# ProPrj_mousring_2025-06-12.net
KiCad netlist of a schematic drawn in EasyEDA Pro
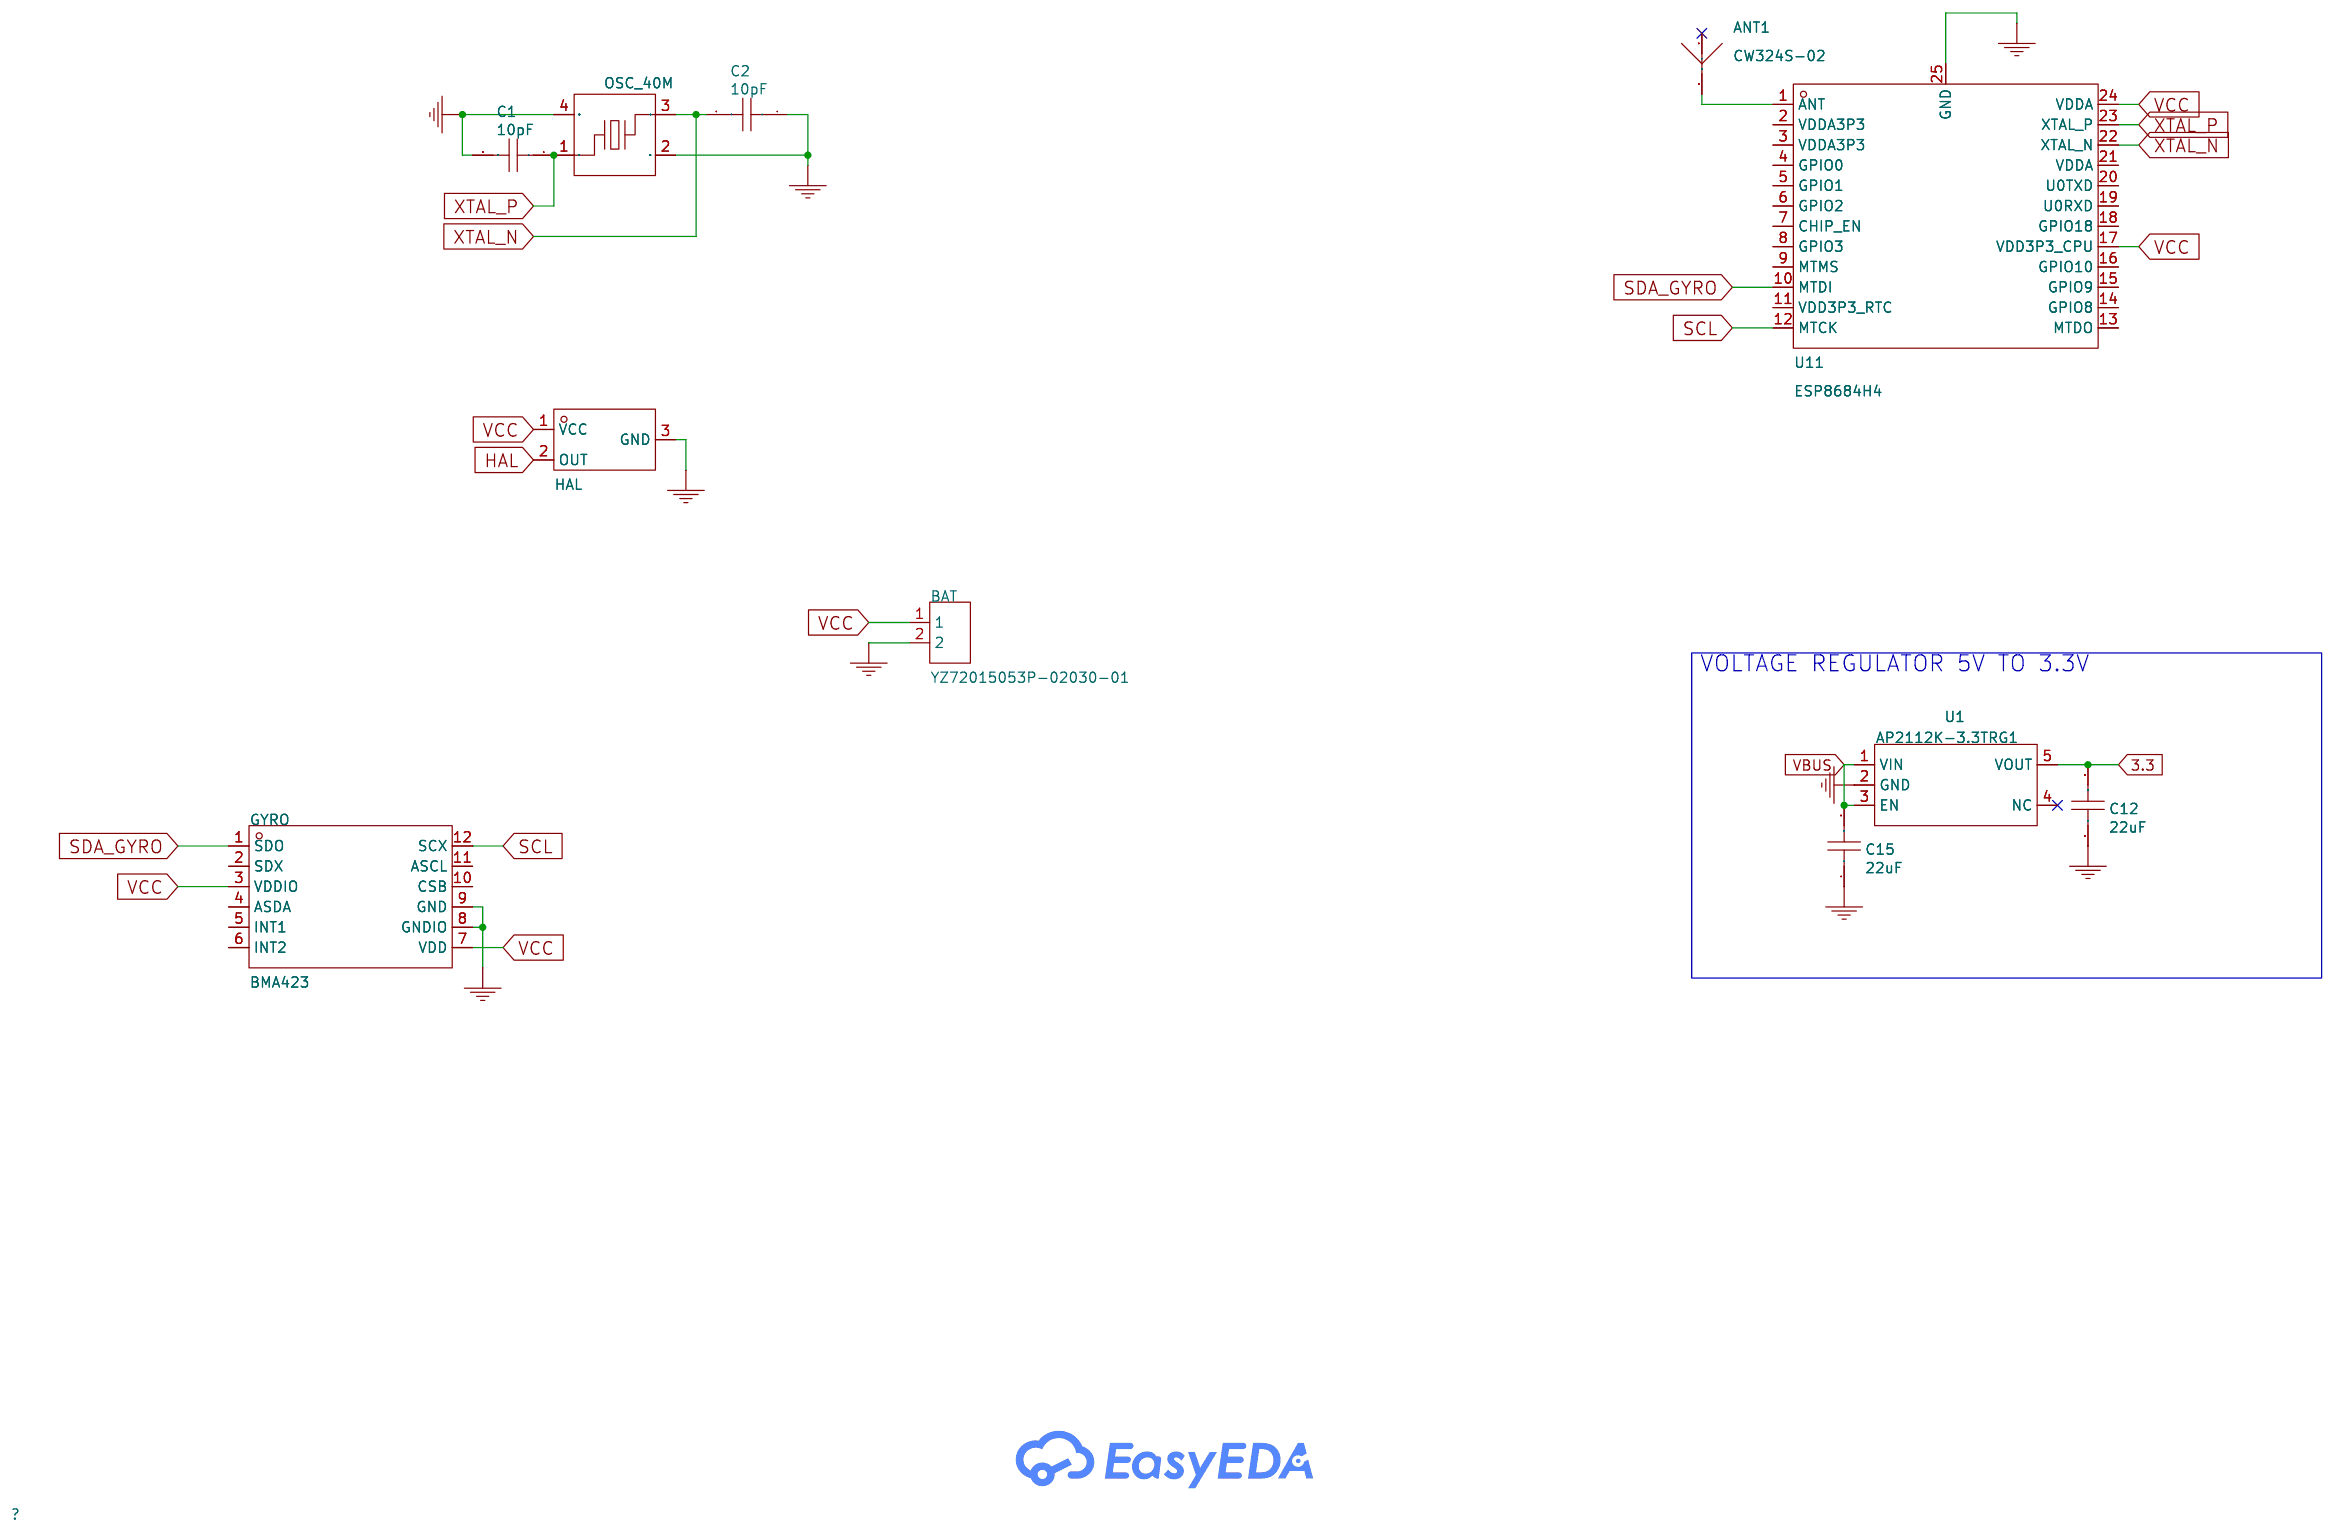
[diagram p0: schematic sheet]

(export (version "E")
  (design (tool "Eeschema 10.0.6"))
  (components
    (comp (ref "ANT1")
      (value "CW324S-02")
      (footprint "easyedapro:ANT-SMD_L3.2-W1.6_CW324S-01")
      (fields (field (name "Manufacturer") "LXC(连兴创)"))
      (libsource (lib "easyedapro") (part "CW324S-02"))
    )
    (comp (ref "BAT")
      (value "YZ72015053P-02030-01")
      (footprint "easyedapro:POGO-SMD_2P-P3.00_YZ72015053P-02030-01")
      (fields (field (name "Manufacturer") "Xinyangze(鑫扬泽)"))
      (libsource (lib "easyedapro") (part "YZ72015053P-02030-01"))
    )
    (comp (ref "C1")
      (value "10pF")
      (footprint "easyedapro:C0402")
      (fields
        (field (name "Manufacturer Part") "CL05C100JB5NNNC")
        (field (name "Manufacturer") "SAMSUNG(三星)")
      )
      (libsource (lib "easyedapro") (part "10pF"))
    )
    (comp (ref "C2")
      (value "10pF")
      (footprint "easyedapro:C0402")
      (fields
        (field (name "Manufacturer Part") "CL05C100JB5NNNC")
        (field (name "Manufacturer") "SAMSUNG(三星)")
      )
      (libsource (lib "easyedapro") (part "10pF"))
    )
    (comp (ref "C12")
      (value "22uF")
      (footprint "easyedapro:C0603")
      (fields
        (field (name "Manufacturer Part") "CL10A226MQ8NRNC")
        (field (name "Manufacturer") "SAMSUNG(三星)")
      )
      (libsource (lib "easyedapro") (part "22uF"))
    )
    (comp (ref "C15")
      (value "22uF")
      (footprint "easyedapro:C0603")
      (fields
        (field (name "Manufacturer Part") "CL10A226MQ8NRNC")
        (field (name "Manufacturer") "SAMSUNG(三星)")
      )
      (libsource (lib "easyedapro") (part "22uF"))
    )
    (comp (ref "GYRO")
      (value "BMA423")
      (footprint "easyedapro:LGA-12_L2.0-W2.0-P0.50-BL")
      (fields (field (name "Manufacturer") "Bosch(博世)"))
      (libsource (lib "easyedapro") (part "BMA423"))
    )
    (comp (ref "U1")
      (value "AP2112K-3.3TRG1")
      (footprint "easyedapro:SOT-25-5_L2.9-W1.6-P0.95-LS2.8-BL")
      (fields (field (name "Manufacturer") "DIODES(美台)") (field (name "Contributor") "LCSC"))
      (libsource (lib "easyedapro") (part "AP2112K-3.3TRG1"))
    )
    (comp (ref "U9")
      (value "HAL")
      (footprint "easyedapro:SOT-23-3_L2.9-W1.6-P1.90-LS2.9-BL")
      (fields (field (name "Manufacturer Part") "HAL3144E") (field (name "Manufacturer") "Hallwee(霍尔微电子)"))
      (libsource (lib "easyedapro") (part "HAL3144E"))
    )
    (comp (ref "U11")
      (value "ESP8684H4")
      (footprint "easyedapro:QFN-24_L4.0-W4.0-P0.50-TL-EP2.8")
      (fields (field (name "Manufacturer") "ESPRESSIF(乐鑫)"))
      (libsource (lib "easyedapro") (part "ESP8684H4"))
    )
    (comp (ref "X1")
      (value "OSC_40M")
      (footprint "easyedapro:CRYSTAL-SMD_4P-L1.6-W1.2-BL")
      (fields
        (field (name "Manufacturer Part") "SX0B40.000F1010F30")
        (field (name "Manufacturer") "SCTF(星通时频)")
        (field (name "Contributor") "lcsc")
      )
      (libsource (lib "easyedapro") (part "40MHz"))
    )
  )
  (nets
    (net (code "1") (name "3.3") (class "Default")
      (node (ref "C12") (pin "2") (pinfunction "2_2") (pintype "unspecified"))
      (node (ref "U1") (pin "5") (pinfunction "VOUT_5") (pintype "unspecified"))
    )
    (net (code "2") (name "GND") (class "Default")
      (node (ref "BAT") (pin "2") (pinfunction "2_2") (pintype "unspecified"))
      (node (ref "C1") (pin "2") (pinfunction "2_2") (pintype "unspecified"))
      (node (ref "C12") (pin "1") (pinfunction "1_1") (pintype "unspecified"))
      (node (ref "C15") (pin "1") (pinfunction "1_1") (pintype "unspecified"))
      (node (ref "C2") (pin "1") (pinfunction "1_1") (pintype "unspecified"))
      (node (ref "GYRO") (pin "8") (pinfunction "GNDIO_8") (pintype "unspecified"))
      (node (ref "GYRO") (pin "9") (pinfunction "GND_9") (pintype "unspecified"))
      (node (ref "U1") (pin "2") (pinfunction "GND_2") (pintype "unspecified"))
      (node (ref "U11") (pin "25") (pinfunction "GND_25") (pintype "unspecified"))
      (node (ref "U9") (pin "3") (pinfunction "GND_3") (pintype "unspecified"))
      (node (ref "X1") (pin "2") (pinfunction "GND_2") (pintype "input"))
      (node (ref "X1") (pin "4") (pinfunction "GND_4") (pintype "input"))
    )
    (net (code "3") (name "HAL") (class "Default")
      (node (ref "U9") (pin "2") (pinfunction "OUT_2") (pintype "unspecified"))
    )
    (net (code "4") (name "Net-(ANT1-ANT)") (class "Default")
      (node (ref "ANT1") (pin "1") (pinfunction "ANT_1") (pintype "unspecified"))
      (node (ref "U11") (pin "1") (pinfunction "ANT_1") (pintype "unspecified"))
    )
    (net (code "5") (name "SCL") (class "Default")
      (node (ref "GYRO") (pin "12") (pinfunction "SCX_12") (pintype "unspecified"))
      (node (ref "U11") (pin "12") (pinfunction "MTCK_12") (pintype "unspecified"))
    )
    (net (code "6") (name "SDA_GYRO") (class "Default")
      (node (ref "GYRO") (pin "1") (pinfunction "SDO_1") (pintype "unspecified"))
      (node (ref "U11") (pin "10") (pinfunction "MTDI_10") (pintype "unspecified"))
    )
    (net (code "7") (name "VBUS") (class "Default")
      (node (ref "C15") (pin "2") (pinfunction "2_2") (pintype "unspecified"))
      (node (ref "U1") (pin "1") (pinfunction "VIN_1") (pintype "unspecified"))
      (node (ref "U1") (pin "3") (pinfunction "EN_3") (pintype "unspecified"))
    )
    (net (code "8") (name "VCC") (class "Default")
      (node (ref "BAT") (pin "1") (pinfunction "1_1") (pintype "unspecified"))
      (node (ref "GYRO") (pin "3") (pinfunction "VDDIO_3") (pintype "unspecified"))
      (node (ref "GYRO") (pin "7") (pinfunction "VDD_7") (pintype "unspecified"))
      (node (ref "U11") (pin "17") (pinfunction "VDD3P3_CPU_17") (pintype "unspecified"))
      (node (ref "U11") (pin "24") (pinfunction "VDDA_24") (pintype "unspecified"))
      (node (ref "U9") (pin "1") (pinfunction "VCC_1") (pintype "unspecified"))
    )
    (net (code "9") (name "XTAL_N") (class "Default")
      (node (ref "C2") (pin "2") (pinfunction "2_2") (pintype "unspecified"))
      (node (ref "U11") (pin "22") (pinfunction "XTAL_N_22") (pintype "unspecified"))
      (node (ref "X1") (pin "3") (pinfunction "3_3") (pintype "input"))
    )
    (net (code "10") (name "XTAL_P") (class "Default")
      (node (ref "C1") (pin "1") (pinfunction "1_1") (pintype "unspecified"))
      (node (ref "U11") (pin "23") (pinfunction "XTAL_P_23") (pintype "unspecified"))
      (node (ref "X1") (pin "1") (pinfunction "1_1") (pintype "input"))
    )
    (net (code "11") (name "unconnected-(ANT1-Pad2)") (class "Default")
      (node (ref "ANT1") (pin "2") (pinfunction "2_2") (pintype "unspecified+no_connect"))
    )
    (net (code "12") (name "unconnected-(GYRO-ASCL-Pad11)") (class "Default")
      (node (ref "GYRO") (pin "11") (pinfunction "ASCL_11") (pintype "unspecified"))
    )
    (net (code "13") (name "unconnected-(GYRO-ASDA-Pad4)") (class "Default")
      (node (ref "GYRO") (pin "4") (pinfunction "ASDA_4") (pintype "unspecified"))
    )
    (net (code "14") (name "unconnected-(GYRO-CSB-Pad10)") (class "Default")
      (node (ref "GYRO") (pin "10") (pinfunction "CSB_10") (pintype "unspecified"))
    )
    (net (code "15") (name "unconnected-(GYRO-INT1-Pad5)") (class "Default")
      (node (ref "GYRO") (pin "5") (pinfunction "INT1_5") (pintype "unspecified"))
    )
    (net (code "16") (name "unconnected-(GYRO-INT2-Pad6)") (class "Default")
      (node (ref "GYRO") (pin "6") (pinfunction "INT2_6") (pintype "unspecified"))
    )
    (net (code "17") (name "unconnected-(GYRO-SDX-Pad2)") (class "Default")
      (node (ref "GYRO") (pin "2") (pinfunction "SDX_2") (pintype "unspecified"))
    )
    (net (code "18") (name "unconnected-(U1-NC-Pad4)") (class "Default")
      (node (ref "U1") (pin "4") (pinfunction "NC_4") (pintype "unspecified+no_connect"))
    )
    (net (code "19") (name "unconnected-(U11-CHIP_EN-Pad7)") (class "Default")
      (node (ref "U11") (pin "7") (pinfunction "CHIP_EN_7") (pintype "unspecified"))
    )
    (net (code "20") (name "unconnected-(U11-GPIO0-Pad4)") (class "Default")
      (node (ref "U11") (pin "4") (pinfunction "GPIO0_4") (pintype "unspecified"))
    )
    (net (code "21") (name "unconnected-(U11-GPIO1-Pad5)") (class "Default")
      (node (ref "U11") (pin "5") (pinfunction "GPIO1_5") (pintype "unspecified"))
    )
    (net (code "22") (name "unconnected-(U11-GPIO2-Pad6)") (class "Default")
      (node (ref "U11") (pin "6") (pinfunction "GPIO2_6") (pintype "unspecified"))
    )
    (net (code "23") (name "unconnected-(U11-GPIO3-Pad8)") (class "Default")
      (node (ref "U11") (pin "8") (pinfunction "GPIO3_8") (pintype "unspecified"))
    )
    (net (code "24") (name "unconnected-(U11-GPIO8-Pad14)") (class "Default")
      (node (ref "U11") (pin "14") (pinfunction "GPIO8_14") (pintype "unspecified"))
    )
    (net (code "25") (name "unconnected-(U11-GPIO9-Pad15)") (class "Default")
      (node (ref "U11") (pin "15") (pinfunction "GPIO9_15") (pintype "unspecified"))
    )
    (net (code "26") (name "unconnected-(U11-GPIO10-Pad16)") (class "Default")
      (node (ref "U11") (pin "16") (pinfunction "GPIO10_16") (pintype "unspecified"))
    )
    (net (code "27") (name "unconnected-(U11-GPIO18-Pad18)") (class "Default")
      (node (ref "U11") (pin "18") (pinfunction "GPIO18_18") (pintype "unspecified"))
    )
    (net (code "28") (name "unconnected-(U11-MTDO-Pad13)") (class "Default")
      (node (ref "U11") (pin "13") (pinfunction "MTDO_13") (pintype "unspecified"))
    )
    (net (code "29") (name "unconnected-(U11-MTMS-Pad9)") (class "Default")
      (node (ref "U11") (pin "9") (pinfunction "MTMS_9") (pintype "unspecified"))
    )
    (net (code "30") (name "unconnected-(U11-U0RXD-Pad19)") (class "Default")
      (node (ref "U11") (pin "19") (pinfunction "U0RXD_19") (pintype "unspecified"))
    )
    (net (code "31") (name "unconnected-(U11-U0TXD-Pad20)") (class "Default")
      (node (ref "U11") (pin "20") (pinfunction "U0TXD_20") (pintype "unspecified"))
    )
    (net (code "32") (name "unconnected-(U11-VDD3P3_RTC-Pad11)") (class "Default")
      (node (ref "U11") (pin "11") (pinfunction "VDD3P3_RTC_11") (pintype "unspecified"))
    )
    (net (code "33") (name "unconnected-(U11-VDDA-Pad21)") (class "Default")
      (node (ref "U11") (pin "21") (pinfunction "VDDA_21") (pintype "unspecified"))
    )
    (net (code "34") (name "unconnected-(U11-VDDA3P3-Pad2)") (class "Default")
      (node (ref "U11") (pin "2") (pinfunction "VDDA3P3_2") (pintype "unspecified"))
    )
    (net (code "35") (name "unconnected-(U11-VDDA3P3-Pad3)") (class "Default")
      (node (ref "U11") (pin "3") (pinfunction "VDDA3P3_3") (pintype "unspecified"))
    )
  )
)
